# SDCARD.net
KiCad netlist of a schematic drawn in Altium Designer
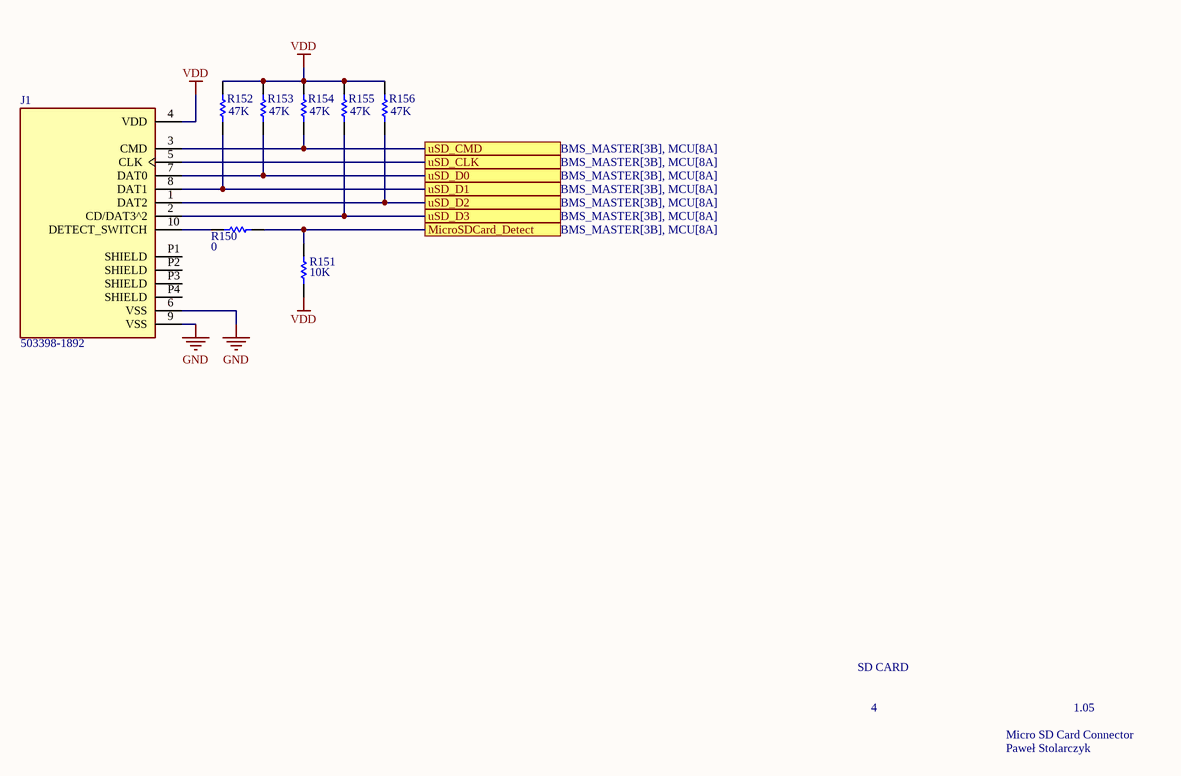
[diagram p0: SDCARD.SchDoc]

(export (version "E")
  (design (tool "Eeschema 10.0.6"))
  (components
    (comp (ref "J1")
      (value "503398-1892")
      (footprint "MOLEX_503398-1892")
      (description "9 (8 + 1) Position Card Connector Secure Digital - microSDâ„¢ Surface Mount, Right Angle Gold")
      (fields (field (name "MP") "5033981892") (field (name "MF") "Molex"))
      (libsource (lib "503398-1892") (part "503398-1892"))
    )
    (comp (ref "R150")
      (value "0")
      (footprint "0402")
      (description "Resistor")
      (fields (field (name "Comment") "Res1") (field (name "PUBLISHER") "Altium Limited"))
      (libsource (lib "Miscellaneous Devices") (part "Res1"))
    )
    (comp (ref "R151")
      (value "10K")
      (footprint "0402")
      (description "Resistor")
      (fields (field (name "Comment") "Res1") (field (name "PUBLISHER") "Altium Limited"))
      (libsource (lib "Miscellaneous Devices") (part "Res1"))
    )
    (comp (ref "R152")
      (value "47K")
      (footprint "0402")
      (description "Resistor")
      (fields (field (name "Comment") "Res1") (field (name "PUBLISHER") "Altium Limited"))
      (libsource (lib "Miscellaneous Devices") (part "Res1"))
    )
    (comp (ref "R153")
      (value "47K")
      (footprint "0402")
      (description "Resistor")
      (fields (field (name "Comment") "Res1") (field (name "PUBLISHER") "Altium Limited"))
      (libsource (lib "Miscellaneous Devices") (part "Res1"))
    )
    (comp (ref "R154")
      (value "47K")
      (footprint "0402")
      (description "Resistor")
      (fields (field (name "Comment") "Res1") (field (name "PUBLISHER") "Altium Limited"))
      (libsource (lib "Miscellaneous Devices") (part "Res1"))
    )
    (comp (ref "R155")
      (value "47K")
      (footprint "0402")
      (description "Resistor")
      (fields (field (name "Comment") "Res1") (field (name "PUBLISHER") "Altium Limited"))
      (libsource (lib "Miscellaneous Devices") (part "Res1"))
    )
    (comp (ref "R156")
      (value "47K")
      (footprint "0402")
      (description "Resistor")
      (fields (field (name "Comment") "Res1") (field (name "PUBLISHER") "Altium Limited"))
      (libsource (lib "Miscellaneous Devices") (part "Res1"))
    )
  )
  (nets
    (net (code "1") (name "/MicroSDCard_Detect") (class "Default")
      (node (ref "R150") (pin "2") (pinfunction "2_2") (pintype "passive"))
      (node (ref "R151") (pin "1") (pinfunction "1_1") (pintype "passive"))
    )
    (net (code "2") (name "/uSD_CLK") (class "Default")
      (node (ref "J1") (pin "5") (pinfunction "CLK_5") (pintype "passive"))
    )
    (net (code "3") (name "/uSD_CMD") (class "Default")
      (node (ref "J1") (pin "3") (pinfunction "CMD_3") (pintype "passive"))
      (node (ref "R154") (pin "1") (pinfunction "1_1") (pintype "passive"))
    )
    (net (code "4") (name "/uSD_D0") (class "Default")
      (node (ref "J1") (pin "7") (pinfunction "DAT0_7") (pintype "passive"))
      (node (ref "R153") (pin "1") (pinfunction "1_1") (pintype "passive"))
    )
    (net (code "5") (name "/uSD_D1") (class "Default")
      (node (ref "J1") (pin "8") (pinfunction "DAT1_8") (pintype "passive"))
      (node (ref "R152") (pin "1") (pinfunction "1_1") (pintype "passive"))
    )
    (net (code "6") (name "/uSD_D2") (class "Default")
      (node (ref "J1") (pin "1") (pinfunction "DAT2_1") (pintype "passive"))
      (node (ref "R156") (pin "1") (pinfunction "1_1") (pintype "passive"))
    )
    (net (code "7") (name "/uSD_D3") (class "Default")
      (node (ref "J1") (pin "2") (pinfunction "CD/DAT3^2_2") (pintype "passive"))
      (node (ref "R155") (pin "1") (pinfunction "1_1") (pintype "passive"))
    )
    (net (code "8") (name "GND") (class "Default")
      (node (ref "J1") (pin "6") (pinfunction "VSS_6") (pintype "power_in"))
      (node (ref "J1") (pin "9") (pinfunction "VSS_9") (pintype "power_in"))
    )
    (net (code "9") (name "Net-(J1-DETECT_SWITCH)") (class "Default")
      (node (ref "J1") (pin "10") (pinfunction "DETECT_SWITCH_10") (pintype "passive"))
      (node (ref "R150") (pin "1") (pinfunction "1_1") (pintype "passive"))
    )
    (net (code "10") (name "VDD") (class "Default")
      (node (ref "J1") (pin "4") (pinfunction "VDD_4") (pintype "power_in"))
      (node (ref "R151") (pin "2") (pinfunction "2_2") (pintype "passive"))
      (node (ref "R152") (pin "2") (pinfunction "2_2") (pintype "passive"))
      (node (ref "R153") (pin "2") (pinfunction "2_2") (pintype "passive"))
      (node (ref "R154") (pin "2") (pinfunction "2_2") (pintype "passive"))
      (node (ref "R155") (pin "2") (pinfunction "2_2") (pintype "passive"))
      (node (ref "R156") (pin "2") (pinfunction "2_2") (pintype "passive"))
    )
    (net (code "11") (name "unconnected-(J1-SHIELD-PadP1)") (class "Default")
      (node (ref "J1") (pin "P1") (pinfunction "SHIELD_P1") (pintype "passive"))
    )
    (net (code "12") (name "unconnected-(J1-SHIELD-PadP2)") (class "Default")
      (node (ref "J1") (pin "P2") (pinfunction "SHIELD_P2") (pintype "passive"))
    )
    (net (code "13") (name "unconnected-(J1-SHIELD-PadP3)") (class "Default")
      (node (ref "J1") (pin "P3") (pinfunction "SHIELD_P3") (pintype "passive"))
    )
    (net (code "14") (name "unconnected-(J1-SHIELD-PadP4)") (class "Default")
      (node (ref "J1") (pin "P4") (pinfunction "SHIELD_P4") (pintype "passive"))
    )
  )
)
